# series_12led.net
KiCad netlist of a schematic drawn in EAGLE
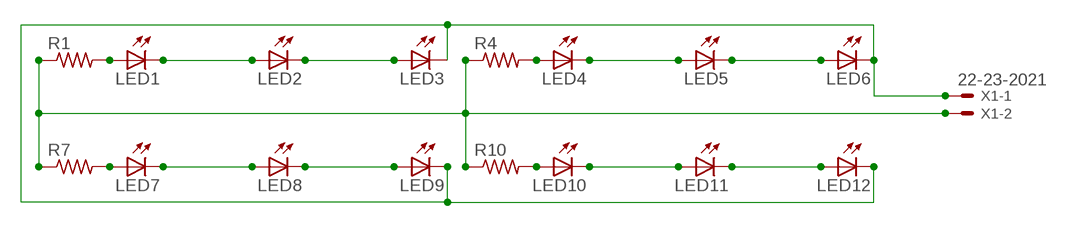
[diagram p0: schematic, sheet 1]

(export (version "E")
  (design (tool "Eeschema 10.0.6"))
  (components
    (comp (ref "LED1")
      (value "LED3MM")
      (footprint "eagle-import:LED3MM")
      (libsource (lib "eagle-import") (part "LED3MM"))
    )
    (comp (ref "LED2")
      (value "LED3MM")
      (footprint "eagle-import:LED3MM")
      (libsource (lib "eagle-import") (part "LED3MM"))
    )
    (comp (ref "LED3")
      (value "LED3MM")
      (footprint "eagle-import:LED3MM")
      (libsource (lib "eagle-import") (part "LED3MM"))
    )
    (comp (ref "LED4")
      (value "LED3MM")
      (footprint "eagle-import:LED3MM")
      (libsource (lib "eagle-import") (part "LED3MM"))
    )
    (comp (ref "LED5")
      (value "LED3MM")
      (footprint "eagle-import:LED3MM")
      (libsource (lib "eagle-import") (part "LED3MM"))
    )
    (comp (ref "LED6")
      (value "LED3MM")
      (footprint "eagle-import:LED3MM")
      (libsource (lib "eagle-import") (part "LED3MM"))
    )
    (comp (ref "LED7")
      (value "LED3MM")
      (footprint "eagle-import:LED3MM")
      (libsource (lib "eagle-import") (part "LED3MM"))
    )
    (comp (ref "LED8")
      (value "LED3MM")
      (footprint "eagle-import:LED3MM")
      (libsource (lib "eagle-import") (part "LED3MM"))
    )
    (comp (ref "LED9")
      (value "LED3MM")
      (footprint "eagle-import:LED3MM")
      (libsource (lib "eagle-import") (part "LED3MM"))
    )
    (comp (ref "LED10")
      (value "LED3MM")
      (footprint "eagle-import:LED3MM")
      (libsource (lib "eagle-import") (part "LED3MM"))
    )
    (comp (ref "LED11")
      (value "LED3MM")
      (footprint "eagle-import:LED3MM")
      (libsource (lib "eagle-import") (part "LED3MM"))
    )
    (comp (ref "LED12")
      (value "LED3MM")
      (footprint "eagle-import:LED3MM")
      (libsource (lib "eagle-import") (part "LED3MM"))
    )
    (comp (ref "R1")
      (value "R-US_0207/10")
      (footprint "eagle-import:0207_10")
      (libsource (lib "eagle-import") (part "R-US_0207/10"))
    )
    (comp (ref "R4")
      (value "R-US_0207/10")
      (footprint "eagle-import:0207_10")
      (libsource (lib "eagle-import") (part "R-US_0207/10"))
    )
    (comp (ref "R7")
      (value "R-US_0207/10")
      (footprint "eagle-import:0207_10")
      (libsource (lib "eagle-import") (part "R-US_0207/10"))
    )
    (comp (ref "R10")
      (value "R-US_0207/10")
      (footprint "eagle-import:0207_10")
      (libsource (lib "eagle-import") (part "R-US_0207/10"))
    )
    (comp (ref "X1")
      (value "22-23-2021")
      (footprint "eagle-import:22-23-2021")
      (fields (field (name "MF") "MOLEX"))
      (libsource (lib "eagle-import") (part "22-23-2021"))
    )
  )
  (nets
    (net (code "1") (name "Net-(LED1-C)") (class "Default")
      (node (ref "LED1") (pin "K") (pinfunction "C_K") (pintype "passive"))
      (node (ref "LED2") (pin "A") (pinfunction "A_A") (pintype "passive"))
    )
    (net (code "2") (name "Net-(LED1-PadA)") (class "Default")
      (node (ref "LED1") (pin "A") (pinfunction "A_A") (pintype "passive"))
      (node (ref "R1") (pin "2") (pinfunction "2_2") (pintype "passive"))
    )
    (net (code "3") (name "Net-(LED2-C)") (class "Default")
      (node (ref "LED2") (pin "K") (pinfunction "C_K") (pintype "passive"))
      (node (ref "LED3") (pin "A") (pinfunction "A_A") (pintype "passive"))
    )
    (net (code "4") (name "Net-(LED4-C)") (class "Default")
      (node (ref "LED4") (pin "K") (pinfunction "C_K") (pintype "passive"))
      (node (ref "LED5") (pin "A") (pinfunction "A_A") (pintype "passive"))
    )
    (net (code "5") (name "Net-(LED4-PadA)") (class "Default")
      (node (ref "LED4") (pin "A") (pinfunction "A_A") (pintype "passive"))
      (node (ref "R4") (pin "2") (pinfunction "2_2") (pintype "passive"))
    )
    (net (code "6") (name "Net-(LED5-C)") (class "Default")
      (node (ref "LED5") (pin "K") (pinfunction "C_K") (pintype "passive"))
      (node (ref "LED6") (pin "A") (pinfunction "A_A") (pintype "passive"))
    )
    (net (code "7") (name "Net-(LED7-C)") (class "Default")
      (node (ref "LED7") (pin "K") (pinfunction "C_K") (pintype "passive"))
      (node (ref "LED8") (pin "A") (pinfunction "A_A") (pintype "passive"))
    )
    (net (code "8") (name "Net-(LED7-PadA)") (class "Default")
      (node (ref "LED7") (pin "A") (pinfunction "A_A") (pintype "passive"))
      (node (ref "R7") (pin "2") (pinfunction "2_2") (pintype "passive"))
    )
    (net (code "9") (name "Net-(LED8-C)") (class "Default")
      (node (ref "LED8") (pin "K") (pinfunction "C_K") (pintype "passive"))
      (node (ref "LED9") (pin "A") (pinfunction "A_A") (pintype "passive"))
    )
    (net (code "10") (name "Net-(LED10-C)") (class "Default")
      (node (ref "LED10") (pin "K") (pinfunction "C_K") (pintype "passive"))
      (node (ref "LED11") (pin "A") (pinfunction "A_A") (pintype "passive"))
    )
    (net (code "11") (name "Net-(LED10-PadA)") (class "Default")
      (node (ref "LED10") (pin "A") (pinfunction "A_A") (pintype "passive"))
      (node (ref "R10") (pin "2") (pinfunction "2_2") (pintype "passive"))
    )
    (net (code "12") (name "Net-(LED11-C)") (class "Default")
      (node (ref "LED11") (pin "K") (pinfunction "C_K") (pintype "passive"))
      (node (ref "LED12") (pin "A") (pinfunction "A_A") (pintype "passive"))
    )
    (net (code "13") (name "Net-(LED12-C)") (class "Default")
      (node (ref "LED12") (pin "K") (pinfunction "C_K") (pintype "passive"))
      (node (ref "LED3") (pin "K") (pinfunction "C_K") (pintype "passive"))
      (node (ref "LED6") (pin "K") (pinfunction "C_K") (pintype "passive"))
      (node (ref "LED9") (pin "K") (pinfunction "C_K") (pintype "passive"))
      (node (ref "X1") (pin "1") (pinfunction "S_1") (pintype "passive"))
    )
    (net (code "14") (name "Net-(X1B-S)") (class "Default")
      (node (ref "R1") (pin "1") (pinfunction "1_1") (pintype "passive"))
      (node (ref "R10") (pin "1") (pinfunction "1_1") (pintype "passive"))
      (node (ref "R4") (pin "1") (pinfunction "1_1") (pintype "passive"))
      (node (ref "R7") (pin "1") (pinfunction "1_1") (pintype "passive"))
      (node (ref "X1") (pin "2") (pinfunction "S_2") (pintype "passive"))
    )
  )
)
